# PWM_Pump_Led.net
KiCad netlist of a schematic drawn in Altium Designer
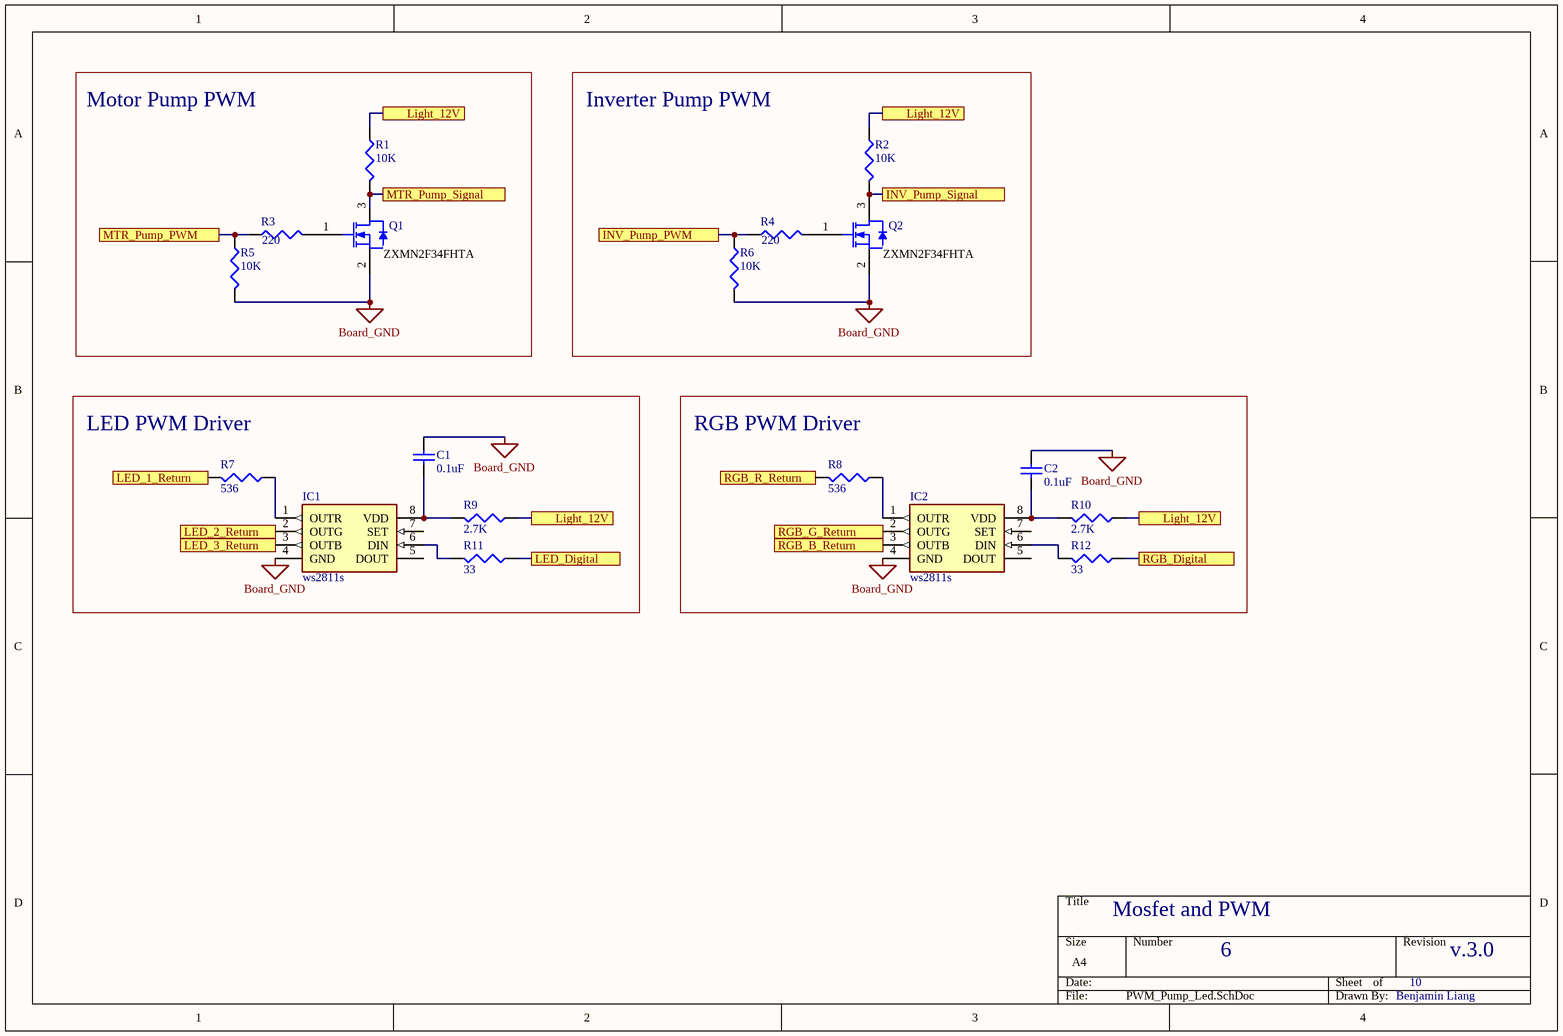
[diagram p0: PWM_Pump_Led.SchDoc]

(export (version "E")
  (design (tool "Eeschema 10.0.6"))
  (components
    (comp (ref "C1")
      (value "0.1uF")
      (footprint "C1206")
      (description "Capacitor (Semiconductor SIM Model)")
      (fields (field (name "PUBLISHER") "Altium Limited"))
      (libsource (lib "Miscellaneous Devices") (part "Cap Semi"))
    )
    (comp (ref "C2")
      (value "0.1uF")
      (footprint "C1206")
      (description "Capacitor (Semiconductor SIM Model)")
      (fields (field (name "PUBLISHER") "Altium Limited"))
      (libsource (lib "Miscellaneous Devices") (part "Cap Semi"))
    )
    (comp (ref "IC1")
      (value "ws2811s")
      (footprint "SamacSys:SOIC127P600X175-8N")
      (description "Integrated Circuit")
      (libsource (lib "*") (part "ws2811s"))
    )
    (comp (ref "IC2")
      (value "ws2811s")
      (footprint "SamacSys:SOIC127P600X175-8N")
      (description "Integrated Circuit")
      (libsource (lib "*") (part "ws2811s"))
    )
    (comp (ref "Q1")
      (value "ZXMN2F34FHTA")
      (footprint "FAIR-SSOT3L-3_V")
      (fields (field (name "MANUFACTURER") "FairchildSemiconductor"))
      (libsource (lib "Altium Content Vault") (part "NEMOS-GSD-3"))
    )
    (comp (ref "Q2")
      (value "ZXMN2F34FHTA")
      (footprint "FAIR-SSOT3L-3_V")
      (fields (field (name "MANUFACTURER") "FairchildSemiconductor"))
      (libsource (lib "Altium Content Vault") (part "NEMOS-GSD-3"))
    )
    (comp (ref "R1")
      (value "10K")
      (footprint "J1-0603")
      (description "Resistor")
      (fields (field (name "PUBLISHER") "Altium Limited"))
      (libsource (lib "Miscellaneous Devices") (part "Res3"))
    )
    (comp (ref "R2")
      (value "10K")
      (footprint "J1-0603")
      (description "Resistor")
      (fields (field (name "PUBLISHER") "Altium Limited"))
      (libsource (lib "Miscellaneous Devices") (part "Res3"))
    )
    (comp (ref "R3")
      (value "220")
      (footprint "J1-0603")
      (description "Resistor")
      (fields (field (name "PUBLISHER") "Altium Limited"))
      (libsource (lib "Miscellaneous Devices") (part "Res3"))
    )
    (comp (ref "R4")
      (value "220")
      (footprint "J1-0603")
      (description "Resistor")
      (fields (field (name "PUBLISHER") "Altium Limited"))
      (libsource (lib "Miscellaneous Devices") (part "Res3"))
    )
    (comp (ref "R5")
      (value "10K")
      (footprint "J1-0603")
      (description "Resistor")
      (fields (field (name "PUBLISHER") "Altium Limited"))
      (libsource (lib "Miscellaneous Devices") (part "Res3"))
    )
    (comp (ref "R6")
      (value "10K")
      (footprint "J1-0603")
      (description "Resistor")
      (fields (field (name "PUBLISHER") "Altium Limited"))
      (libsource (lib "Miscellaneous Devices") (part "Res3"))
    )
    (comp (ref "R7")
      (value "536")
      (footprint "J1-0603")
      (description "Resistor")
      (fields (field (name "PUBLISHER") "Altium Limited"))
      (libsource (lib "Miscellaneous Devices") (part "Res3"))
    )
    (comp (ref "R8")
      (value "536")
      (footprint "J1-0603")
      (description "Resistor")
      (fields (field (name "PUBLISHER") "Altium Limited"))
      (libsource (lib "Miscellaneous Devices") (part "Res3"))
    )
    (comp (ref "R9")
      (value "2.7K")
      (footprint "J1-0603")
      (description "Resistor")
      (fields (field (name "PUBLISHER") "Altium Limited"))
      (libsource (lib "Miscellaneous Devices") (part "Res3"))
    )
    (comp (ref "R10")
      (value "2.7K")
      (footprint "J1-0603")
      (description "Resistor")
      (fields (field (name "PUBLISHER") "Altium Limited"))
      (libsource (lib "Miscellaneous Devices") (part "Res3"))
    )
    (comp (ref "R11")
      (value "33")
      (footprint "J1-0603")
      (description "Resistor")
      (fields (field (name "PUBLISHER") "Altium Limited"))
      (libsource (lib "Miscellaneous Devices") (part "Res3"))
    )
    (comp (ref "R12")
      (value "33")
      (footprint "J1-0603")
      (description "Resistor")
      (fields (field (name "PUBLISHER") "Altium Limited"))
      (libsource (lib "Miscellaneous Devices") (part "Res3"))
    )
  )
  (nets
    (net (code "1") (name "/INV_Pump_PWM") (class "Default")
      (node (ref "R4") (pin "1") (pinfunction "1_1") (pintype "passive"))
      (node (ref "R6") (pin "1") (pinfunction "1_1") (pintype "passive"))
    )
    (net (code "2") (name "/INV_Pump_Signal") (class "Default")
      (node (ref "Q2") (pin "3") (pinfunction "D_3") (pintype "passive"))
      (node (ref "R2") (pin "2") (pinfunction "2_2") (pintype "passive"))
    )
    (net (code "3") (name "/LED_1_Return") (class "Default")
      (node (ref "R7") (pin "2") (pinfunction "2_2") (pintype "passive"))
    )
    (net (code "4") (name "/LED_2_Return") (class "Default")
      (node (ref "IC1") (pin "2") (pinfunction "OUTG_2") (pintype "output"))
    )
    (net (code "5") (name "/LED_3_Return") (class "Default")
      (node (ref "IC1") (pin "3") (pinfunction "OUTB_3") (pintype "output"))
    )
    (net (code "6") (name "/LED_Digital") (class "Default")
      (node (ref "R11") (pin "1") (pinfunction "1_1") (pintype "passive"))
    )
    (net (code "7") (name "/Light_12V") (class "Default")
      (node (ref "R1") (pin "1") (pinfunction "1_1") (pintype "passive"))
      (node (ref "R10") (pin "1") (pinfunction "1_1") (pintype "passive"))
      (node (ref "R2") (pin "1") (pinfunction "1_1") (pintype "passive"))
      (node (ref "R9") (pin "1") (pinfunction "1_1") (pintype "passive"))
    )
    (net (code "8") (name "/MTR_Pump_PWM") (class "Default")
      (node (ref "R3") (pin "1") (pinfunction "1_1") (pintype "passive"))
      (node (ref "R5") (pin "1") (pinfunction "1_1") (pintype "passive"))
    )
    (net (code "9") (name "/MTR_Pump_Signal") (class "Default")
      (node (ref "Q1") (pin "3") (pinfunction "D_3") (pintype "passive"))
      (node (ref "R1") (pin "2") (pinfunction "2_2") (pintype "passive"))
    )
    (net (code "10") (name "/RGB_B_Return") (class "Default")
      (node (ref "IC2") (pin "3") (pinfunction "OUTB_3") (pintype "output"))
    )
    (net (code "11") (name "/RGB_Digital") (class "Default")
      (node (ref "R12") (pin "1") (pinfunction "1_1") (pintype "passive"))
    )
    (net (code "12") (name "/RGB_G_Return") (class "Default")
      (node (ref "IC2") (pin "2") (pinfunction "OUTG_2") (pintype "output"))
    )
    (net (code "13") (name "/RGB_R_Return") (class "Default")
      (node (ref "R8") (pin "2") (pinfunction "2_2") (pintype "passive"))
    )
    (net (code "14") (name "Board_GND") (class "Default")
      (node (ref "C1") (pin "1") (pinfunction "1_1") (pintype "passive"))
      (node (ref "C2") (pin "1") (pinfunction "1_1") (pintype "passive"))
      (node (ref "IC1") (pin "4") (pinfunction "GND_4") (pintype "power_in"))
      (node (ref "IC2") (pin "4") (pinfunction "GND_4") (pintype "power_in"))
      (node (ref "Q1") (pin "2") (pinfunction "S_2") (pintype "passive"))
      (node (ref "Q2") (pin "2") (pinfunction "S_2") (pintype "passive"))
      (node (ref "R5") (pin "2") (pinfunction "2_2") (pintype "passive"))
      (node (ref "R6") (pin "2") (pinfunction "2_2") (pintype "passive"))
    )
    (net (code "15") (name "Net-(IC1-DIN)") (class "Default")
      (node (ref "IC1") (pin "6") (pinfunction "DIN_6") (pintype "input"))
      (node (ref "R11") (pin "2") (pinfunction "2_2") (pintype "passive"))
    )
    (net (code "16") (name "Net-(IC1-OUTR)") (class "Default")
      (node (ref "IC1") (pin "1") (pinfunction "OUTR_1") (pintype "output"))
      (node (ref "R7") (pin "1") (pinfunction "1_1") (pintype "passive"))
    )
    (net (code "17") (name "Net-(IC1-VDD)") (class "Default")
      (node (ref "C1") (pin "2") (pinfunction "2_2") (pintype "passive"))
      (node (ref "IC1") (pin "8") (pinfunction "VDD_8") (pintype "power_in"))
      (node (ref "R9") (pin "2") (pinfunction "2_2") (pintype "passive"))
    )
    (net (code "18") (name "Net-(IC2-DIN)") (class "Default")
      (node (ref "IC2") (pin "6") (pinfunction "DIN_6") (pintype "input"))
      (node (ref "R12") (pin "2") (pinfunction "2_2") (pintype "passive"))
    )
    (net (code "19") (name "Net-(IC2-OUTR)") (class "Default")
      (node (ref "IC2") (pin "1") (pinfunction "OUTR_1") (pintype "output"))
      (node (ref "R8") (pin "1") (pinfunction "1_1") (pintype "passive"))
    )
    (net (code "20") (name "Net-(IC2-VDD)") (class "Default")
      (node (ref "C2") (pin "2") (pinfunction "2_2") (pintype "passive"))
      (node (ref "IC2") (pin "8") (pinfunction "VDD_8") (pintype "power_in"))
      (node (ref "R10") (pin "2") (pinfunction "2_2") (pintype "passive"))
    )
    (net (code "21") (name "Net-(Q1-G)") (class "Default")
      (node (ref "Q1") (pin "1") (pinfunction "G_1") (pintype "passive"))
      (node (ref "R3") (pin "2") (pinfunction "2_2") (pintype "passive"))
    )
    (net (code "22") (name "Net-(Q2-G)") (class "Default")
      (node (ref "Q2") (pin "1") (pinfunction "G_1") (pintype "passive"))
      (node (ref "R4") (pin "2") (pinfunction "2_2") (pintype "passive"))
    )
    (net (code "23") (name "unconnected-(IC1-DOUT-Pad5)") (class "Default")
      (node (ref "IC1") (pin "5") (pinfunction "DOUT_5") (pintype "passive"))
    )
    (net (code "24") (name "unconnected-(IC1-SET-Pad7)") (class "Default")
      (node (ref "IC1") (pin "7") (pinfunction "SET_7") (pintype "input"))
    )
    (net (code "25") (name "unconnected-(IC2-DOUT-Pad5)") (class "Default")
      (node (ref "IC2") (pin "5") (pinfunction "DOUT_5") (pintype "passive"))
    )
    (net (code "26") (name "unconnected-(IC2-SET-Pad7)") (class "Default")
      (node (ref "IC2") (pin "7") (pinfunction "SET_7") (pintype "input"))
    )
  )
)
